# sch_Connet_IMU.net
KiCad netlist of a schematic drawn in Altium Designer
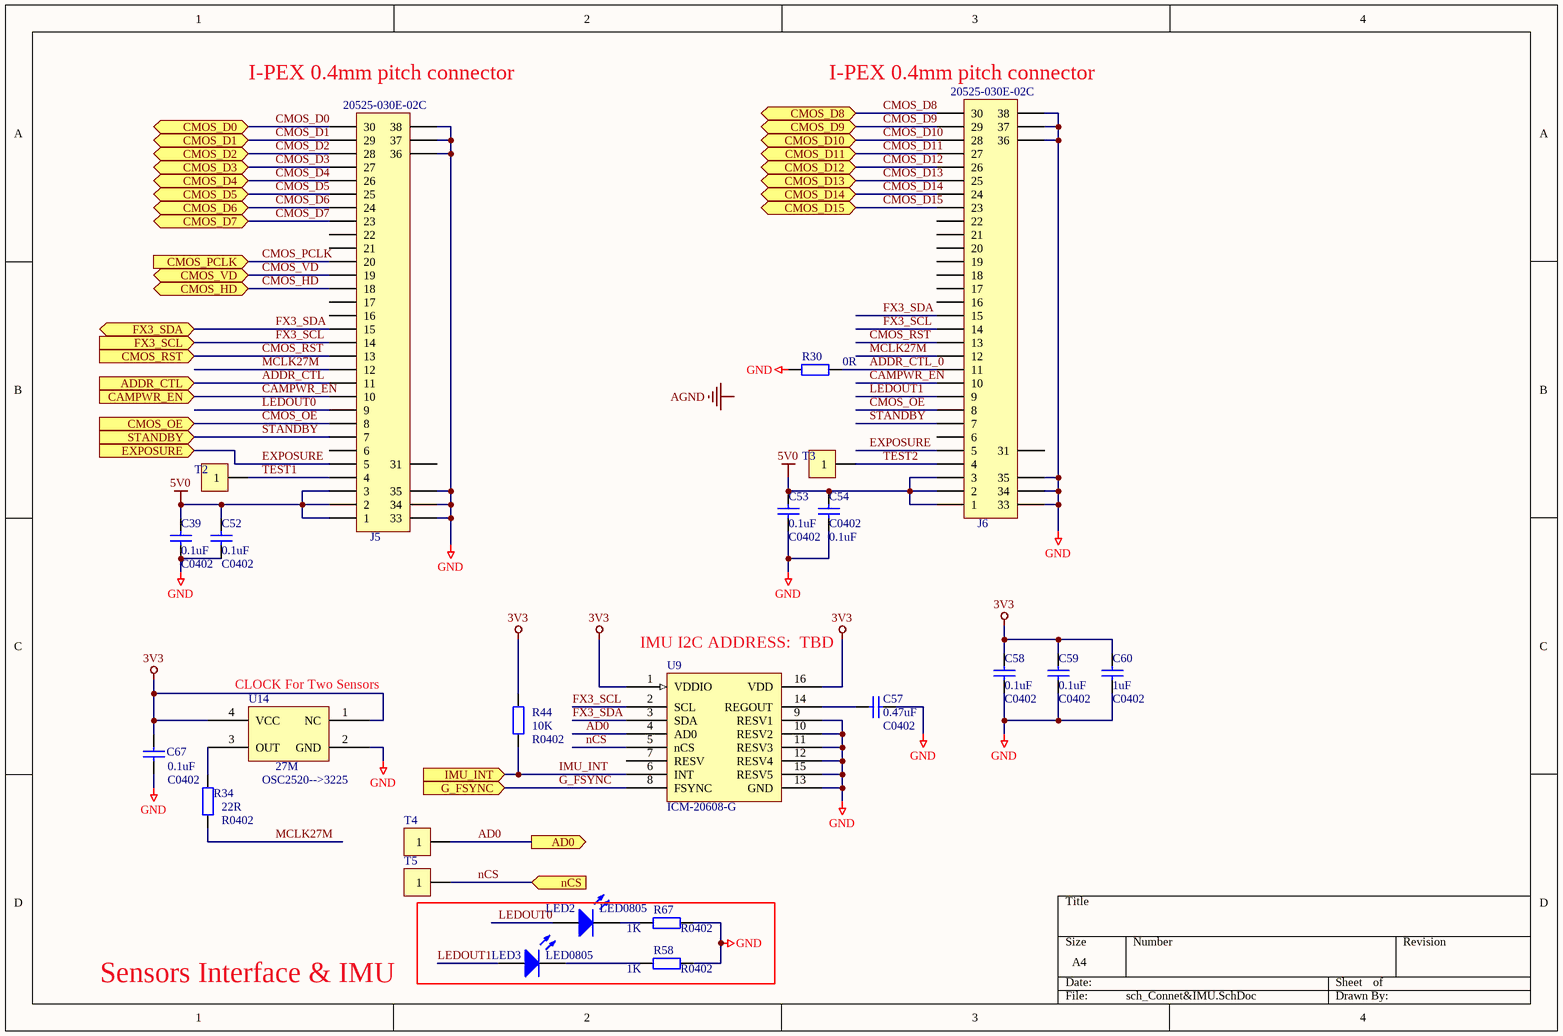
[diagram p0: sch_Connet&IMU.SchDoc]

(export (version "E")
  (design (tool "Eeschema 10.0.6"))
  (components
    (comp (ref "C39")
      (value "0.1uF")
      (footprint "0402C")
      (description "Capacitor")
      (fields (field (name "ALTIUM_VALUE") "C0402") (field (name "PUBLISHER") "Altium Limited"))
      (libsource (lib "Miscellaneous Devices") (part "Cap"))
    )
    (comp (ref "C52")
      (value "0.1uF")
      (footprint "0402C")
      (description "Capacitor")
      (fields (field (name "ALTIUM_VALUE") "C0402") (field (name "PUBLISHER") "Altium Limited"))
      (libsource (lib "Miscellaneous Devices") (part "Cap"))
    )
    (comp (ref "C53")
      (value "0.1uF")
      (footprint "0402C")
      (description "Capacitor")
      (fields (field (name "ALTIUM_VALUE") "C0402") (field (name "PUBLISHER") "Altium Limited"))
      (libsource (lib "Miscellaneous Devices") (part "Cap"))
    )
    (comp (ref "C54")
      (value "0.1uF")
      (footprint "0402C")
      (description "Capacitor")
      (fields (field (name "ALTIUM_VALUE") "C0402") (field (name "PUBLISHER") "Altium Limited"))
      (libsource (lib "Miscellaneous Devices") (part "Cap"))
    )
    (comp (ref "C57")
      (value "0.47uF")
      (footprint "0402C")
      (description "Capacitor")
      (fields (field (name "ALTIUM_VALUE") "C0402") (field (name "PUBLISHER") "Altium Limited"))
      (libsource (lib "Miscellaneous Devices") (part "Cap"))
    )
    (comp (ref "C58")
      (value "0.1uF")
      (footprint "0402C")
      (description "Capacitor")
      (fields (field (name "ALTIUM_VALUE") "C0402") (field (name "PUBLISHER") "Altium Limited"))
      (libsource (lib "Miscellaneous Devices") (part "Cap"))
    )
    (comp (ref "C59")
      (value "0.1uF")
      (footprint "0402C")
      (description "Capacitor")
      (fields (field (name "ALTIUM_VALUE") "C0402") (field (name "PUBLISHER") "Altium Limited"))
      (libsource (lib "Miscellaneous Devices") (part "Cap"))
    )
    (comp (ref "C60")
      (value "1uF")
      (footprint "0402C")
      (description "Capacitor")
      (fields (field (name "ALTIUM_VALUE") "C0402") (field (name "PUBLISHER") "Altium Limited"))
      (libsource (lib "Miscellaneous Devices") (part "Cap"))
    )
    (comp (ref "C67")
      (value "0.1uF")
      (footprint "0402C")
      (description "Capacitor")
      (fields (field (name "ALTIUM_VALUE") "C0402") (field (name "PUBLISHER") "Altium Limited"))
      (libsource (lib "Miscellaneous Devices") (part "Cap"))
    )
    (comp (ref "J5")
      (value "20525-030E-02C")
      (footprint "HSA30_P40L196W42H10_20525")
      (libsource (lib "SZG") (part "20525-030E-02C"))
    )
    (comp (ref "J6")
      (value "20525-030E-02C")
      (footprint "HSA30_P40L196W42H10_20525")
      (libsource (lib "SZG") (part "20525-030E-02C"))
    )
    (comp (ref "LED2")
      (value "LED0805")
      (footprint "LED0805A_L210W100H60")
      (description "发光二级管")
      (libsource (lib "TXW") (part "LED"))
    )
    (comp (ref "LED3")
      (value "LED0805")
      (footprint "LED0805A_L210W100H60")
      (description "发光二级管")
      (libsource (lib "TXW") (part "LED"))
    )
    (comp (ref "R30")
      (value "0R")
      (footprint "0402R")
      (description "Resistor")
      (fields (field (name "PUBLISHER") "Altium Limited"))
      (libsource (lib "") (part "Res2_1"))
    )
    (comp (ref "R34")
      (value "22R")
      (footprint "0402R")
      (description "Resistor")
      (fields (field (name "ALTIUM_VALUE") "R0402") (field (name "PUBLISHER") "Altium Limited"))
      (libsource (lib "Miscellaneous Devices") (part "Res2"))
    )
    (comp (ref "R44")
      (value "10K")
      (footprint "0402R")
      (description "Resistor")
      (fields (field (name "ALTIUM_VALUE") "R0402") (field (name "PUBLISHER") "Altium Limited"))
      (libsource (lib "Miscellaneous Devices") (part "Res2"))
    )
    (comp (ref "R58")
      (value "1K")
      (footprint "0402R")
      (description "Resistor")
      (fields (field (name "ALTIUM_VALUE") "R0402") (field (name "PUBLISHER") "Altium Limited"))
      (libsource (lib "") (part "Res2_1"))
    )
    (comp (ref "R67")
      (value "1K")
      (footprint "0402R")
      (description "Resistor")
      (fields (field (name "ALTIUM_VALUE") "R0402") (field (name "PUBLISHER") "Altium Limited"))
      (libsource (lib "") (part "Res2_1"))
    )
    (comp (ref "T2")
      (value "CON1")
      (footprint "PAD_TP_D1.2")
      (description "Connector")
      (libsource (lib "SuperSchLib") (part "CON1"))
    )
    (comp (ref "T3")
      (value "CON1")
      (footprint "PAD_TP_D1.2")
      (description "Connector")
      (libsource (lib "SuperSchLib") (part "CON1"))
    )
    (comp (ref "T4")
      (value "CON1")
      (footprint "PAD_TP_D1.2")
      (description "Connector")
      (libsource (lib "SuperSchLib") (part "CON1"))
    )
    (comp (ref "T5")
      (value "CON1")
      (footprint "PAD_TP_D1.2")
      (description "Connector")
      (libsource (lib "SuperSchLib") (part "CON1"))
    )
    (comp (ref "U9")
      (value "ICM-20608-G")
      (footprint "LGA16_P50L30W30H08")
      (libsource (lib "SZG") (part "ICM-20608-G"))
    )
    (comp (ref "U14")
      (value "OSC2520-->3225")
      (footprint "XTAL_3225")
      (description "Simple Package Xtal Oscillator")
      (libsource (lib "常用晶振器件图SCH") (part "XTAL-SPXO"))
    )
  )
  (nets
    (net (code "1") (name "/AD0") (class "Default")
      (node (ref "T4") (pin "1") (pinfunction "1_1") (pintype "passive"))
      (node (ref "U9") (pin "4") (pinfunction "AD0_4") (pintype "passive"))
    )
    (net (code "2") (name "/ADDR_CTL") (class "Default")
      (node (ref "J5") (pin "11") (pinfunction "11_11") (pintype "passive"))
    )
    (net (code "3") (name "/ADDR_CTL_0") (class "Default")
      (node (ref "J6") (pin "11") (pinfunction "11_11") (pintype "passive"))
      (node (ref "R30") (pin "1") (pinfunction "1_1") (pintype "passive"))
    )
    (net (code "4") (name "/CAMPWR_EN") (class "Default")
      (node (ref "J5") (pin "10") (pinfunction "10_10") (pintype "passive"))
      (node (ref "J6") (pin "10") (pinfunction "10_10") (pintype "passive"))
    )
    (net (code "5") (name "/CMOS_D0") (class "Default")
      (node (ref "J5") (pin "30") (pinfunction "30_30") (pintype "passive"))
    )
    (net (code "6") (name "/CMOS_D1") (class "Default")
      (node (ref "J5") (pin "29") (pinfunction "29_29") (pintype "passive"))
    )
    (net (code "7") (name "/CMOS_D2") (class "Default")
      (node (ref "J5") (pin "28") (pinfunction "28_28") (pintype "passive"))
    )
    (net (code "8") (name "/CMOS_D3") (class "Default")
      (node (ref "J5") (pin "27") (pinfunction "27_27") (pintype "passive"))
    )
    (net (code "9") (name "/CMOS_D4") (class "Default")
      (node (ref "J5") (pin "26") (pinfunction "26_26") (pintype "passive"))
    )
    (net (code "10") (name "/CMOS_D5") (class "Default")
      (node (ref "J5") (pin "25") (pinfunction "25_25") (pintype "passive"))
    )
    (net (code "11") (name "/CMOS_D6") (class "Default")
      (node (ref "J5") (pin "24") (pinfunction "24_24") (pintype "passive"))
    )
    (net (code "12") (name "/CMOS_D7") (class "Default")
      (node (ref "J5") (pin "23") (pinfunction "23_23") (pintype "passive"))
    )
    (net (code "13") (name "/CMOS_D8") (class "Default")
      (node (ref "J6") (pin "30") (pinfunction "30_30") (pintype "passive"))
    )
    (net (code "14") (name "/CMOS_D9") (class "Default")
      (node (ref "J6") (pin "29") (pinfunction "29_29") (pintype "passive"))
    )
    (net (code "15") (name "/CMOS_D10") (class "Default")
      (node (ref "J6") (pin "28") (pinfunction "28_28") (pintype "passive"))
    )
    (net (code "16") (name "/CMOS_D11") (class "Default")
      (node (ref "J6") (pin "27") (pinfunction "27_27") (pintype "passive"))
    )
    (net (code "17") (name "/CMOS_D12") (class "Default")
      (node (ref "J6") (pin "26") (pinfunction "26_26") (pintype "passive"))
    )
    (net (code "18") (name "/CMOS_D13") (class "Default")
      (node (ref "J6") (pin "25") (pinfunction "25_25") (pintype "passive"))
    )
    (net (code "19") (name "/CMOS_D14") (class "Default")
      (node (ref "J6") (pin "24") (pinfunction "24_24") (pintype "passive"))
    )
    (net (code "20") (name "/CMOS_D15") (class "Default")
      (node (ref "J6") (pin "23") (pinfunction "23_23") (pintype "passive"))
    )
    (net (code "21") (name "/CMOS_HD") (class "Default")
      (node (ref "J5") (pin "18") (pinfunction "18_18") (pintype "passive"))
    )
    (net (code "22") (name "/CMOS_OE") (class "Default")
      (node (ref "J5") (pin "8") (pinfunction "8_8") (pintype "passive"))
      (node (ref "J6") (pin "8") (pinfunction "8_8") (pintype "passive"))
    )
    (net (code "23") (name "/CMOS_PCLK") (class "Default")
      (node (ref "J5") (pin "20") (pinfunction "20_20") (pintype "passive"))
    )
    (net (code "24") (name "/CMOS_RST") (class "Default")
      (node (ref "J5") (pin "13") (pinfunction "13_13") (pintype "passive"))
      (node (ref "J6") (pin "13") (pinfunction "13_13") (pintype "passive"))
    )
    (net (code "25") (name "/CMOS_VD") (class "Default")
      (node (ref "J5") (pin "19") (pinfunction "19_19") (pintype "passive"))
    )
    (net (code "26") (name "/EXPOSURE") (class "Default")
      (node (ref "J5") (pin "5") (pinfunction "5_5") (pintype "passive"))
      (node (ref "J6") (pin "5") (pinfunction "5_5") (pintype "passive"))
    )
    (net (code "27") (name "/FX3_SCL") (class "Default")
      (node (ref "J5") (pin "14") (pinfunction "14_14") (pintype "passive"))
      (node (ref "J6") (pin "14") (pinfunction "14_14") (pintype "passive"))
      (node (ref "U9") (pin "2") (pinfunction "SCL_2") (pintype "passive"))
    )
    (net (code "28") (name "/FX3_SDA") (class "Default")
      (node (ref "J5") (pin "15") (pinfunction "15_15") (pintype "passive"))
      (node (ref "J6") (pin "15") (pinfunction "15_15") (pintype "passive"))
      (node (ref "U9") (pin "3") (pinfunction "SDA_3") (pintype "passive"))
    )
    (net (code "29") (name "/G_FSYNC") (class "Default")
      (node (ref "U9") (pin "8") (pinfunction "FSYNC_8") (pintype "passive"))
    )
    (net (code "30") (name "/IMU_INT") (class "Default")
      (node (ref "R44") (pin "1") (pinfunction "1_1") (pintype "passive"))
      (node (ref "U9") (pin "6") (pinfunction "INT_6") (pintype "passive"))
    )
    (net (code "31") (name "/LEDOUT0") (class "Default")
      (node (ref "J5") (pin "9") (pinfunction "9_9") (pintype "passive"))
      (node (ref "LED2") (pin "1") (pinfunction "A_1") (pintype "passive"))
    )
    (net (code "32") (name "/LEDOUT1") (class "Default")
      (node (ref "J6") (pin "9") (pinfunction "9_9") (pintype "passive"))
      (node (ref "LED3") (pin "1") (pinfunction "A_1") (pintype "passive"))
    )
    (net (code "33") (name "/MCLK27M") (class "Default")
      (node (ref "J5") (pin "12") (pinfunction "12_12") (pintype "passive"))
      (node (ref "J6") (pin "12") (pinfunction "12_12") (pintype "passive"))
      (node (ref "R34") (pin "1") (pinfunction "1_1") (pintype "passive"))
    )
    (net (code "34") (name "/STANDBY") (class "Default")
      (node (ref "J5") (pin "7") (pinfunction "7_7") (pintype "passive"))
      (node (ref "J6") (pin "7") (pinfunction "7_7") (pintype "passive"))
    )
    (net (code "35") (name "/TEST1") (class "Default")
      (node (ref "J5") (pin "4") (pinfunction "4_4") (pintype "passive"))
      (node (ref "T2") (pin "1") (pinfunction "1_1") (pintype "passive"))
    )
    (net (code "36") (name "/TEST2") (class "Default")
      (node (ref "J6") (pin "4") (pinfunction "4_4") (pintype "passive"))
      (node (ref "T3") (pin "1") (pinfunction "1_1") (pintype "passive"))
    )
    (net (code "37") (name "/nCS") (class "Default")
      (node (ref "T5") (pin "1") (pinfunction "1_1") (pintype "passive"))
      (node (ref "U9") (pin "5") (pinfunction "nCS_5") (pintype "passive"))
    )
    (net (code "38") (name "3V3") (class "Default")
      (node (ref "C58") (pin "2") (pinfunction "2_2") (pintype "passive"))
      (node (ref "C59") (pin "2") (pinfunction "2_2") (pintype "passive"))
      (node (ref "C60") (pin "2") (pinfunction "2_2") (pintype "passive"))
      (node (ref "C67") (pin "2") (pinfunction "2_2") (pintype "passive"))
      (node (ref "R44") (pin "2") (pinfunction "2_2") (pintype "passive"))
      (node (ref "U14") (pin "1") (pinfunction "NC_1") (pintype "passive"))
      (node (ref "U14") (pin "4") (pinfunction "VCC_4") (pintype "passive"))
      (node (ref "U9") (pin "1") (pinfunction "VDDIO_1") (pintype "input"))
      (node (ref "U9") (pin "16") (pinfunction "VDD_16") (pintype "passive"))
    )
    (net (code "39") (name "5V0") (class "Default")
      (node (ref "C39") (pin "2") (pinfunction "2_2") (pintype "passive"))
      (node (ref "C52") (pin "2") (pinfunction "2_2") (pintype "passive"))
      (node (ref "C53") (pin "2") (pinfunction "2_2") (pintype "passive"))
      (node (ref "C54") (pin "2") (pinfunction "2_2") (pintype "passive"))
      (node (ref "J5") (pin "1") (pinfunction "1_1") (pintype "passive"))
      (node (ref "J5") (pin "2") (pinfunction "2_2") (pintype "passive"))
      (node (ref "J5") (pin "3") (pinfunction "3_3") (pintype "passive"))
      (node (ref "J6") (pin "1") (pinfunction "1_1") (pintype "passive"))
      (node (ref "J6") (pin "2") (pinfunction "2_2") (pintype "passive"))
      (node (ref "J6") (pin "3") (pinfunction "3_3") (pintype "passive"))
    )
    (net (code "41") (name "GND") (class "Default")
      (node (ref "C39") (pin "1") (pinfunction "1_1") (pintype "passive"))
      (node (ref "C52") (pin "1") (pinfunction "1_1") (pintype "passive"))
      (node (ref "C53") (pin "1") (pinfunction "1_1") (pintype "passive"))
      (node (ref "C54") (pin "1") (pinfunction "1_1") (pintype "passive"))
      (node (ref "C57") (pin "1") (pinfunction "1_1") (pintype "passive"))
      (node (ref "C58") (pin "1") (pinfunction "1_1") (pintype "passive"))
      (node (ref "C59") (pin "1") (pinfunction "1_1") (pintype "passive"))
      (node (ref "C60") (pin "1") (pinfunction "1_1") (pintype "passive"))
      (node (ref "C67") (pin "1") (pinfunction "1_1") (pintype "passive"))
      (node (ref "J5") (pin "33") (pinfunction "33_33") (pintype "passive"))
      (node (ref "J5") (pin "34") (pinfunction "34_34") (pintype "passive"))
      (node (ref "J5") (pin "35") (pinfunction "35_35") (pintype "passive"))
      (node (ref "J5") (pin "36") (pinfunction "36_36") (pintype "passive"))
      (node (ref "J5") (pin "37") (pinfunction "37_37") (pintype "passive"))
      (node (ref "J5") (pin "38") (pinfunction "38_38") (pintype "passive"))
      (node (ref "J6") (pin "33") (pinfunction "33_33") (pintype "passive"))
      (node (ref "J6") (pin "34") (pinfunction "34_34") (pintype "passive"))
      (node (ref "J6") (pin "35") (pinfunction "35_35") (pintype "passive"))
      (node (ref "J6") (pin "36") (pinfunction "36_36") (pintype "passive"))
      (node (ref "J6") (pin "37") (pinfunction "37_37") (pintype "passive"))
      (node (ref "J6") (pin "38") (pinfunction "38_38") (pintype "passive"))
      (node (ref "R30") (pin "2") (pinfunction "2_2") (pintype "passive"))
      (node (ref "R58") (pin "1") (pinfunction "1_1") (pintype "passive"))
      (node (ref "R67") (pin "1") (pinfunction "1_1") (pintype "passive"))
      (node (ref "U14") (pin "2") (pinfunction "GND_2") (pintype "passive"))
      (node (ref "U9") (pin "10") (pinfunction "RESV2_10") (pintype "passive"))
      (node (ref "U9") (pin "11") (pinfunction "RESV3_11") (pintype "passive"))
      (node (ref "U9") (pin "12") (pinfunction "RESV4_12") (pintype "passive"))
      (node (ref "U9") (pin "13") (pinfunction "GND_13") (pintype "passive"))
      (node (ref "U9") (pin "15") (pinfunction "RESV5_15") (pintype "passive"))
      (node (ref "U9") (pin "9") (pinfunction "RESV1_9") (pintype "passive"))
    )
    (net (code "42") (name "Net-(LED2-K)") (class "Default")
      (node (ref "LED2") (pin "2") (pinfunction "K_2") (pintype "passive"))
      (node (ref "R67") (pin "2") (pinfunction "2_2") (pintype "passive"))
    )
    (net (code "43") (name "Net-(LED3-K)") (class "Default")
      (node (ref "LED3") (pin "2") (pinfunction "K_2") (pintype "passive"))
      (node (ref "R58") (pin "2") (pinfunction "2_2") (pintype "passive"))
    )
    (net (code "44") (name "Net-(U9-REGOUT)") (class "Default")
      (node (ref "C57") (pin "2") (pinfunction "2_2") (pintype "passive"))
      (node (ref "U9") (pin "14") (pinfunction "REGOUT_14") (pintype "passive"))
    )
    (net (code "45") (name "Net-(U14-OUT)") (class "Default")
      (node (ref "R34") (pin "2") (pinfunction "2_2") (pintype "passive"))
      (node (ref "U14") (pin "3") (pinfunction "OUT_3") (pintype "passive"))
    )
    (net (code "46") (name "unconnected-(J5-Pad6)") (class "Default")
      (node (ref "J5") (pin "6") (pinfunction "6_6") (pintype "passive"))
    )
    (net (code "47") (name "unconnected-(J5-Pad16)") (class "Default")
      (node (ref "J5") (pin "16") (pinfunction "16_16") (pintype "passive"))
    )
    (net (code "48") (name "unconnected-(J5-Pad17)") (class "Default")
      (node (ref "J5") (pin "17") (pinfunction "17_17") (pintype "passive"))
    )
    (net (code "49") (name "unconnected-(J5-Pad21)") (class "Default")
      (node (ref "J5") (pin "21") (pinfunction "21_21") (pintype "passive"))
    )
    (net (code "50") (name "unconnected-(J5-Pad22)") (class "Default")
      (node (ref "J5") (pin "22") (pinfunction "22_22") (pintype "passive"))
    )
    (net (code "51") (name "unconnected-(J5-Pad31)") (class "Default")
      (node (ref "J5") (pin "31") (pinfunction "31_31") (pintype "passive"))
    )
    (net (code "52") (name "unconnected-(J6-Pad6)") (class "Default")
      (node (ref "J6") (pin "6") (pinfunction "6_6") (pintype "passive"))
    )
    (net (code "53") (name "unconnected-(J6-Pad16)") (class "Default")
      (node (ref "J6") (pin "16") (pinfunction "16_16") (pintype "passive"))
    )
    (net (code "54") (name "unconnected-(J6-Pad17)") (class "Default")
      (node (ref "J6") (pin "17") (pinfunction "17_17") (pintype "passive"))
    )
    (net (code "55") (name "unconnected-(J6-Pad18)") (class "Default")
      (node (ref "J6") (pin "18") (pinfunction "18_18") (pintype "passive"))
    )
    (net (code "56") (name "unconnected-(J6-Pad19)") (class "Default")
      (node (ref "J6") (pin "19") (pinfunction "19_19") (pintype "passive"))
    )
    (net (code "57") (name "unconnected-(J6-Pad20)") (class "Default")
      (node (ref "J6") (pin "20") (pinfunction "20_20") (pintype "passive"))
    )
    (net (code "58") (name "unconnected-(J6-Pad21)") (class "Default")
      (node (ref "J6") (pin "21") (pinfunction "21_21") (pintype "passive"))
    )
    (net (code "59") (name "unconnected-(J6-Pad22)") (class "Default")
      (node (ref "J6") (pin "22") (pinfunction "22_22") (pintype "passive"))
    )
    (net (code "60") (name "unconnected-(J6-Pad31)") (class "Default")
      (node (ref "J6") (pin "31") (pinfunction "31_31") (pintype "passive"))
    )
    (net (code "61") (name "unconnected-(U9-RESV-Pad7)") (class "Default")
      (node (ref "U9") (pin "7") (pinfunction "RESV_7") (pintype "passive"))
    )
  )
)
